# bac-bmb.net
KiCad netlist of a schematic drawn in EAGLE
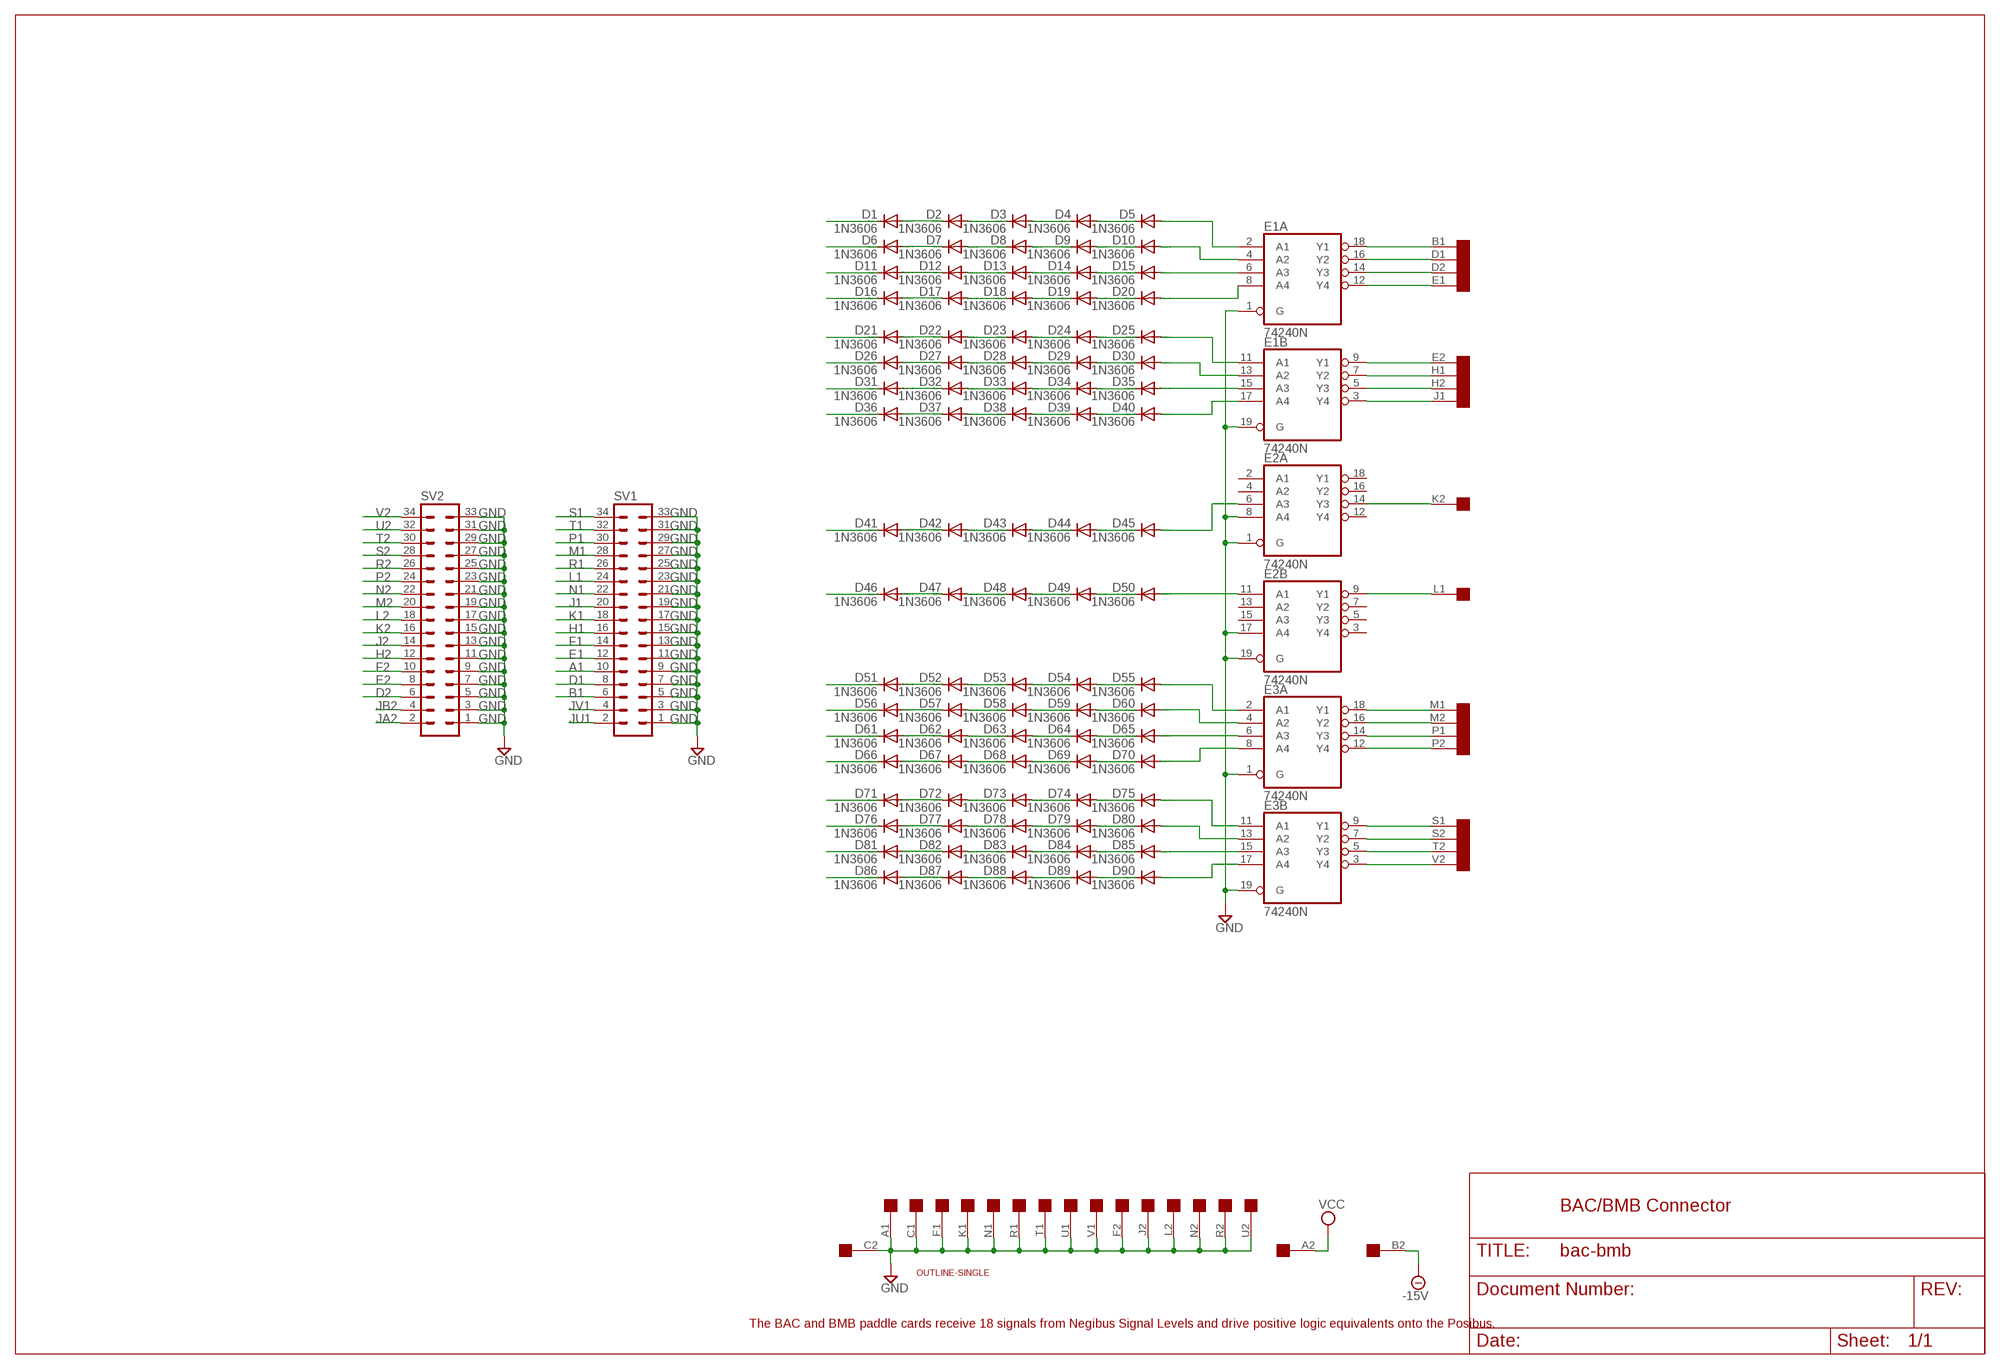
[diagram p0: schematic, sheet 1]

(export (version "E")
  (design (tool "Eeschema 10.0.6"))
  (components
    (comp (ref "D1")
      (value "1N3606")
      (footprint "eagle-import:DO35-10")
      (libsource (lib "eagle-import") (part "DIODE-DO35-10"))
    )
    (comp (ref "D2")
      (value "1N3606")
      (footprint "eagle-import:DO35-10")
      (libsource (lib "eagle-import") (part "DIODE-DO35-10"))
    )
    (comp (ref "D3")
      (value "1N3606")
      (footprint "eagle-import:DO35-10")
      (libsource (lib "eagle-import") (part "DIODE-DO35-10"))
    )
    (comp (ref "D4")
      (value "1N3606")
      (footprint "eagle-import:DO35-10")
      (libsource (lib "eagle-import") (part "DIODE-DO35-10"))
    )
    (comp (ref "D5")
      (value "1N3606")
      (footprint "eagle-import:DO35-10")
      (libsource (lib "eagle-import") (part "DIODE-DO35-10"))
    )
    (comp (ref "D6")
      (value "1N3606")
      (footprint "eagle-import:DO35-10")
      (libsource (lib "eagle-import") (part "DIODE-DO35-10"))
    )
    (comp (ref "D7")
      (value "1N3606")
      (footprint "eagle-import:DO35-10")
      (libsource (lib "eagle-import") (part "DIODE-DO35-10"))
    )
    (comp (ref "D8")
      (value "1N3606")
      (footprint "eagle-import:DO35-10")
      (libsource (lib "eagle-import") (part "DIODE-DO35-10"))
    )
    (comp (ref "D9")
      (value "1N3606")
      (footprint "eagle-import:DO35-10")
      (libsource (lib "eagle-import") (part "DIODE-DO35-10"))
    )
    (comp (ref "D10")
      (value "1N3606")
      (footprint "eagle-import:DO35-10")
      (libsource (lib "eagle-import") (part "DIODE-DO35-10"))
    )
    (comp (ref "D11")
      (value "1N3606")
      (footprint "eagle-import:DO35-10")
      (libsource (lib "eagle-import") (part "DIODE-DO35-10"))
    )
    (comp (ref "D12")
      (value "1N3606")
      (footprint "eagle-import:DO35-10")
      (libsource (lib "eagle-import") (part "DIODE-DO35-10"))
    )
    (comp (ref "D13")
      (value "1N3606")
      (footprint "eagle-import:DO35-10")
      (libsource (lib "eagle-import") (part "DIODE-DO35-10"))
    )
    (comp (ref "D14")
      (value "1N3606")
      (footprint "eagle-import:DO35-10")
      (libsource (lib "eagle-import") (part "DIODE-DO35-10"))
    )
    (comp (ref "D15")
      (value "1N3606")
      (footprint "eagle-import:DO35-10")
      (libsource (lib "eagle-import") (part "DIODE-DO35-10"))
    )
    (comp (ref "D16")
      (value "1N3606")
      (footprint "eagle-import:DO35-10")
      (libsource (lib "eagle-import") (part "DIODE-DO35-10"))
    )
    (comp (ref "D17")
      (value "1N3606")
      (footprint "eagle-import:DO35-10")
      (libsource (lib "eagle-import") (part "DIODE-DO35-10"))
    )
    (comp (ref "D18")
      (value "1N3606")
      (footprint "eagle-import:DO35-10")
      (libsource (lib "eagle-import") (part "DIODE-DO35-10"))
    )
    (comp (ref "D19")
      (value "1N3606")
      (footprint "eagle-import:DO35-10")
      (libsource (lib "eagle-import") (part "DIODE-DO35-10"))
    )
    (comp (ref "D20")
      (value "1N3606")
      (footprint "eagle-import:DO35-10")
      (libsource (lib "eagle-import") (part "DIODE-DO35-10"))
    )
    (comp (ref "D21")
      (value "1N3606")
      (footprint "eagle-import:DO35-10")
      (libsource (lib "eagle-import") (part "DIODE-DO35-10"))
    )
    (comp (ref "D22")
      (value "1N3606")
      (footprint "eagle-import:DO35-10")
      (libsource (lib "eagle-import") (part "DIODE-DO35-10"))
    )
    (comp (ref "D23")
      (value "1N3606")
      (footprint "eagle-import:DO35-10")
      (libsource (lib "eagle-import") (part "DIODE-DO35-10"))
    )
    (comp (ref "D24")
      (value "1N3606")
      (footprint "eagle-import:DO35-10")
      (libsource (lib "eagle-import") (part "DIODE-DO35-10"))
    )
    (comp (ref "D25")
      (value "1N3606")
      (footprint "eagle-import:DO35-10")
      (libsource (lib "eagle-import") (part "DIODE-DO35-10"))
    )
    (comp (ref "D26")
      (value "1N3606")
      (footprint "eagle-import:DO35-10")
      (libsource (lib "eagle-import") (part "DIODE-DO35-10"))
    )
    (comp (ref "D27")
      (value "1N3606")
      (footprint "eagle-import:DO35-10")
      (libsource (lib "eagle-import") (part "DIODE-DO35-10"))
    )
    (comp (ref "D28")
      (value "1N3606")
      (footprint "eagle-import:DO35-10")
      (libsource (lib "eagle-import") (part "DIODE-DO35-10"))
    )
    (comp (ref "D29")
      (value "1N3606")
      (footprint "eagle-import:DO35-10")
      (libsource (lib "eagle-import") (part "DIODE-DO35-10"))
    )
    (comp (ref "D30")
      (value "1N3606")
      (footprint "eagle-import:DO35-10")
      (libsource (lib "eagle-import") (part "DIODE-DO35-10"))
    )
    (comp (ref "D31")
      (value "1N3606")
      (footprint "eagle-import:DO35-10")
      (libsource (lib "eagle-import") (part "DIODE-DO35-10"))
    )
    (comp (ref "D32")
      (value "1N3606")
      (footprint "eagle-import:DO35-10")
      (libsource (lib "eagle-import") (part "DIODE-DO35-10"))
    )
    (comp (ref "D33")
      (value "1N3606")
      (footprint "eagle-import:DO35-10")
      (libsource (lib "eagle-import") (part "DIODE-DO35-10"))
    )
    (comp (ref "D34")
      (value "1N3606")
      (footprint "eagle-import:DO35-10")
      (libsource (lib "eagle-import") (part "DIODE-DO35-10"))
    )
    (comp (ref "D35")
      (value "1N3606")
      (footprint "eagle-import:DO35-10")
      (libsource (lib "eagle-import") (part "DIODE-DO35-10"))
    )
    (comp (ref "D36")
      (value "1N3606")
      (footprint "eagle-import:DO35-10")
      (libsource (lib "eagle-import") (part "DIODE-DO35-10"))
    )
    (comp (ref "D37")
      (value "1N3606")
      (footprint "eagle-import:DO35-10")
      (libsource (lib "eagle-import") (part "DIODE-DO35-10"))
    )
    (comp (ref "D38")
      (value "1N3606")
      (footprint "eagle-import:DO35-10")
      (libsource (lib "eagle-import") (part "DIODE-DO35-10"))
    )
    (comp (ref "D39")
      (value "1N3606")
      (footprint "eagle-import:DO35-10")
      (libsource (lib "eagle-import") (part "DIODE-DO35-10"))
    )
    (comp (ref "D40")
      (value "1N3606")
      (footprint "eagle-import:DO35-10")
      (libsource (lib "eagle-import") (part "DIODE-DO35-10"))
    )
    (comp (ref "D41")
      (value "1N3606")
      (footprint "eagle-import:DO35-10")
      (libsource (lib "eagle-import") (part "DIODE-DO35-10"))
    )
    (comp (ref "D42")
      (value "1N3606")
      (footprint "eagle-import:DO35-10")
      (libsource (lib "eagle-import") (part "DIODE-DO35-10"))
    )
    (comp (ref "D43")
      (value "1N3606")
      (footprint "eagle-import:DO35-10")
      (libsource (lib "eagle-import") (part "DIODE-DO35-10"))
    )
    (comp (ref "D44")
      (value "1N3606")
      (footprint "eagle-import:DO35-10")
      (libsource (lib "eagle-import") (part "DIODE-DO35-10"))
    )
    (comp (ref "D45")
      (value "1N3606")
      (footprint "eagle-import:DO35-10")
      (libsource (lib "eagle-import") (part "DIODE-DO35-10"))
    )
    (comp (ref "D46")
      (value "1N3606")
      (footprint "eagle-import:DO35-10")
      (libsource (lib "eagle-import") (part "DIODE-DO35-10"))
    )
    (comp (ref "D47")
      (value "1N3606")
      (footprint "eagle-import:DO35-10")
      (libsource (lib "eagle-import") (part "DIODE-DO35-10"))
    )
    (comp (ref "D48")
      (value "1N3606")
      (footprint "eagle-import:DO35-10")
      (libsource (lib "eagle-import") (part "DIODE-DO35-10"))
    )
    (comp (ref "D49")
      (value "1N3606")
      (footprint "eagle-import:DO35-10")
      (libsource (lib "eagle-import") (part "DIODE-DO35-10"))
    )
    (comp (ref "D50")
      (value "1N3606")
      (footprint "eagle-import:DO35-10")
      (libsource (lib "eagle-import") (part "DIODE-DO35-10"))
    )
    (comp (ref "D51")
      (value "1N3606")
      (footprint "eagle-import:DO35-10")
      (libsource (lib "eagle-import") (part "DIODE-DO35-10"))
    )
    (comp (ref "D52")
      (value "1N3606")
      (footprint "eagle-import:DO35-10")
      (libsource (lib "eagle-import") (part "DIODE-DO35-10"))
    )
    (comp (ref "D53")
      (value "1N3606")
      (footprint "eagle-import:DO35-10")
      (libsource (lib "eagle-import") (part "DIODE-DO35-10"))
    )
    (comp (ref "D54")
      (value "1N3606")
      (footprint "eagle-import:DO35-10")
      (libsource (lib "eagle-import") (part "DIODE-DO35-10"))
    )
    (comp (ref "D55")
      (value "1N3606")
      (footprint "eagle-import:DO35-10")
      (libsource (lib "eagle-import") (part "DIODE-DO35-10"))
    )
    (comp (ref "D56")
      (value "1N3606")
      (footprint "eagle-import:DO35-10")
      (libsource (lib "eagle-import") (part "DIODE-DO35-10"))
    )
    (comp (ref "D57")
      (value "1N3606")
      (footprint "eagle-import:DO35-10")
      (libsource (lib "eagle-import") (part "DIODE-DO35-10"))
    )
    (comp (ref "D58")
      (value "1N3606")
      (footprint "eagle-import:DO35-10")
      (libsource (lib "eagle-import") (part "DIODE-DO35-10"))
    )
    (comp (ref "D59")
      (value "1N3606")
      (footprint "eagle-import:DO35-10")
      (libsource (lib "eagle-import") (part "DIODE-DO35-10"))
    )
    (comp (ref "D60")
      (value "1N3606")
      (footprint "eagle-import:DO35-10")
      (libsource (lib "eagle-import") (part "DIODE-DO35-10"))
    )
    (comp (ref "D61")
      (value "1N3606")
      (footprint "eagle-import:DO35-10")
      (libsource (lib "eagle-import") (part "DIODE-DO35-10"))
    )
    (comp (ref "D62")
      (value "1N3606")
      (footprint "eagle-import:DO35-10")
      (libsource (lib "eagle-import") (part "DIODE-DO35-10"))
    )
    (comp (ref "D63")
      (value "1N3606")
      (footprint "eagle-import:DO35-10")
      (libsource (lib "eagle-import") (part "DIODE-DO35-10"))
    )
    (comp (ref "D64")
      (value "1N3606")
      (footprint "eagle-import:DO35-10")
      (libsource (lib "eagle-import") (part "DIODE-DO35-10"))
    )
    (comp (ref "D65")
      (value "1N3606")
      (footprint "eagle-import:DO35-10")
      (libsource (lib "eagle-import") (part "DIODE-DO35-10"))
    )
    (comp (ref "D66")
      (value "1N3606")
      (footprint "eagle-import:DO35-10")
      (libsource (lib "eagle-import") (part "DIODE-DO35-10"))
    )
    (comp (ref "D67")
      (value "1N3606")
      (footprint "eagle-import:DO35-10")
      (libsource (lib "eagle-import") (part "DIODE-DO35-10"))
    )
    (comp (ref "D68")
      (value "1N3606")
      (footprint "eagle-import:DO35-10")
      (libsource (lib "eagle-import") (part "DIODE-DO35-10"))
    )
    (comp (ref "D69")
      (value "1N3606")
      (footprint "eagle-import:DO35-10")
      (libsource (lib "eagle-import") (part "DIODE-DO35-10"))
    )
    (comp (ref "D70")
      (value "1N3606")
      (footprint "eagle-import:DO35-10")
      (libsource (lib "eagle-import") (part "DIODE-DO35-10"))
    )
    (comp (ref "D71")
      (value "1N3606")
      (footprint "eagle-import:DO35-10")
      (libsource (lib "eagle-import") (part "DIODE-DO35-10"))
    )
    (comp (ref "D72")
      (value "1N3606")
      (footprint "eagle-import:DO35-10")
      (libsource (lib "eagle-import") (part "DIODE-DO35-10"))
    )
    (comp (ref "D73")
      (value "1N3606")
      (footprint "eagle-import:DO35-10")
      (libsource (lib "eagle-import") (part "DIODE-DO35-10"))
    )
    (comp (ref "D74")
      (value "1N3606")
      (footprint "eagle-import:DO35-10")
      (libsource (lib "eagle-import") (part "DIODE-DO35-10"))
    )
    (comp (ref "D75")
      (value "1N3606")
      (footprint "eagle-import:DO35-10")
      (libsource (lib "eagle-import") (part "DIODE-DO35-10"))
    )
    (comp (ref "D76")
      (value "1N3606")
      (footprint "eagle-import:DO35-10")
      (libsource (lib "eagle-import") (part "DIODE-DO35-10"))
    )
    (comp (ref "D77")
      (value "1N3606")
      (footprint "eagle-import:DO35-10")
      (libsource (lib "eagle-import") (part "DIODE-DO35-10"))
    )
    (comp (ref "D78")
      (value "1N3606")
      (footprint "eagle-import:DO35-10")
      (libsource (lib "eagle-import") (part "DIODE-DO35-10"))
    )
    (comp (ref "D79")
      (value "1N3606")
      (footprint "eagle-import:DO35-10")
      (libsource (lib "eagle-import") (part "DIODE-DO35-10"))
    )
    (comp (ref "D80")
      (value "1N3606")
      (footprint "eagle-import:DO35-10")
      (libsource (lib "eagle-import") (part "DIODE-DO35-10"))
    )
    (comp (ref "D81")
      (value "1N3606")
      (footprint "eagle-import:DO35-10")
      (libsource (lib "eagle-import") (part "DIODE-DO35-10"))
    )
    (comp (ref "D82")
      (value "1N3606")
      (footprint "eagle-import:DO35-10")
      (libsource (lib "eagle-import") (part "DIODE-DO35-10"))
    )
    (comp (ref "D83")
      (value "1N3606")
      (footprint "eagle-import:DO35-10")
      (libsource (lib "eagle-import") (part "DIODE-DO35-10"))
    )
    (comp (ref "D84")
      (value "1N3606")
      (footprint "eagle-import:DO35-10")
      (libsource (lib "eagle-import") (part "DIODE-DO35-10"))
    )
    (comp (ref "D85")
      (value "1N3606")
      (footprint "eagle-import:DO35-10")
      (libsource (lib "eagle-import") (part "DIODE-DO35-10"))
    )
    (comp (ref "D86")
      (value "1N3606")
      (footprint "eagle-import:DO35-10")
      (libsource (lib "eagle-import") (part "DIODE-DO35-10"))
    )
    (comp (ref "D87")
      (value "1N3606")
      (footprint "eagle-import:DO35-10")
      (libsource (lib "eagle-import") (part "DIODE-DO35-10"))
    )
    (comp (ref "D88")
      (value "1N3606")
      (footprint "eagle-import:DO35-10")
      (libsource (lib "eagle-import") (part "DIODE-DO35-10"))
    )
    (comp (ref "D89")
      (value "1N3606")
      (footprint "eagle-import:DO35-10")
      (libsource (lib "eagle-import") (part "DIODE-DO35-10"))
    )
    (comp (ref "D90")
      (value "1N3606")
      (footprint "eagle-import:DO35-10")
      (libsource (lib "eagle-import") (part "DIODE-DO35-10"))
    )
    (comp (ref "E1")
      (value "74240N")
      (footprint "eagle-import:DIL20")
      (libsource (lib "eagle-import") (part "74240NLS"))
    )
    (comp (ref "E2")
      (value "74240N")
      (footprint "eagle-import:DIL20")
      (libsource (lib "eagle-import") (part "74240NLS"))
    )
    (comp (ref "E3")
      (value "74240N")
      (footprint "eagle-import:DIL20")
      (libsource (lib "eagle-import") (part "74240NLS"))
    )
    (comp (ref "SV1")
      (value "MA17-2")
      (footprint "eagle-import:MA17-2")
      (libsource (lib "eagle-import") (part "MA17-2"))
    )
    (comp (ref "SV2")
      (value "MA17-2")
      (footprint "eagle-import:MA17-2")
      (libsource (lib "eagle-import") (part "MA17-2"))
    )
    (comp (ref "U$1")
      (value "SINGLE")
      (footprint "eagle-import:EDGE-CON2")
      (libsource (lib "eagle-import") (part "SINGLE"))
    )
    (comp (ref "U$2")
      (value "OUTLINE-SINGLE")
      (footprint "eagle-import:SINGLE")
      (libsource (lib "eagle-import") (part "OUTLINE-SINGLE"))
    )
  )
  (nets
    (net (code "1") (name "-15V") (class "Default")
      (node (ref "U$1") (pin "B2") (pinfunction "1_B2") (pintype "bidirectional"))
    )
    (net (code "2") (name "/A1") (class "Default")
      (node (ref "SV1") (pin "10") (pinfunction "10_10") (pintype "passive"))
    )
    (net (code "3") (name "/B1") (class "Default")
      (node (ref "D1") (pin "C") (pinfunction "C_C") (pintype "passive"))
      (node (ref "SV1") (pin "6") (pinfunction "6_6") (pintype "passive"))
    )
    (net (code "4") (name "/D1") (class "Default")
      (node (ref "D6") (pin "C") (pinfunction "C_C") (pintype "passive"))
      (node (ref "SV1") (pin "8") (pinfunction "8_8") (pintype "passive"))
    )
    (net (code "5") (name "/D2") (class "Default")
      (node (ref "D11") (pin "C") (pinfunction "C_C") (pintype "passive"))
      (node (ref "SV2") (pin "6") (pinfunction "6_6") (pintype "passive"))
    )
    (net (code "6") (name "/E1") (class "Default")
      (node (ref "D16") (pin "C") (pinfunction "C_C") (pintype "passive"))
      (node (ref "SV1") (pin "12") (pinfunction "12_12") (pintype "passive"))
    )
    (net (code "7") (name "/E2") (class "Default")
      (node (ref "D21") (pin "C") (pinfunction "C_C") (pintype "passive"))
      (node (ref "SV2") (pin "8") (pinfunction "8_8") (pintype "passive"))
    )
    (net (code "8") (name "/F1") (class "Default")
      (node (ref "SV1") (pin "14") (pinfunction "14_14") (pintype "passive"))
    )
    (net (code "9") (name "/F2") (class "Default")
      (node (ref "SV2") (pin "10") (pinfunction "10_10") (pintype "passive"))
    )
    (net (code "10") (name "/H1") (class "Default")
      (node (ref "D26") (pin "C") (pinfunction "C_C") (pintype "passive"))
      (node (ref "SV1") (pin "16") (pinfunction "16_16") (pintype "passive"))
    )
    (net (code "11") (name "/H2") (class "Default")
      (node (ref "D31") (pin "C") (pinfunction "C_C") (pintype "passive"))
      (node (ref "SV2") (pin "12") (pinfunction "12_12") (pintype "passive"))
    )
    (net (code "12") (name "/J1") (class "Default")
      (node (ref "D36") (pin "C") (pinfunction "C_C") (pintype "passive"))
      (node (ref "SV1") (pin "20") (pinfunction "20_20") (pintype "passive"))
    )
    (net (code "13") (name "/J2") (class "Default")
      (node (ref "SV2") (pin "14") (pinfunction "14_14") (pintype "passive"))
    )
    (net (code "14") (name "/JA2") (class "Default")
      (node (ref "SV2") (pin "2") (pinfunction "2_2") (pintype "passive"))
    )
    (net (code "15") (name "/JB2") (class "Default")
      (node (ref "SV2") (pin "4") (pinfunction "4_4") (pintype "passive"))
    )
    (net (code "16") (name "/JU1") (class "Default")
      (node (ref "SV1") (pin "2") (pinfunction "2_2") (pintype "passive"))
    )
    (net (code "17") (name "/JV1") (class "Default")
      (node (ref "SV1") (pin "4") (pinfunction "4_4") (pintype "passive"))
    )
    (net (code "18") (name "/K1") (class "Default")
      (node (ref "SV1") (pin "18") (pinfunction "18_18") (pintype "passive"))
    )
    (net (code "19") (name "/K2") (class "Default")
      (node (ref "D41") (pin "C") (pinfunction "C_C") (pintype "passive"))
      (node (ref "SV2") (pin "16") (pinfunction "16_16") (pintype "passive"))
    )
    (net (code "20") (name "/L1") (class "Default")
      (node (ref "D46") (pin "C") (pinfunction "C_C") (pintype "passive"))
      (node (ref "SV1") (pin "24") (pinfunction "24_24") (pintype "passive"))
    )
    (net (code "21") (name "/L2") (class "Default")
      (node (ref "SV2") (pin "18") (pinfunction "18_18") (pintype "passive"))
    )
    (net (code "22") (name "/M1") (class "Default")
      (node (ref "D51") (pin "C") (pinfunction "C_C") (pintype "passive"))
      (node (ref "SV1") (pin "28") (pinfunction "28_28") (pintype "passive"))
    )
    (net (code "23") (name "/M2") (class "Default")
      (node (ref "D56") (pin "C") (pinfunction "C_C") (pintype "passive"))
      (node (ref "SV2") (pin "20") (pinfunction "20_20") (pintype "passive"))
    )
    (net (code "24") (name "/N1") (class "Default")
      (node (ref "SV1") (pin "22") (pinfunction "22_22") (pintype "passive"))
    )
    (net (code "25") (name "/N2") (class "Default")
      (node (ref "SV2") (pin "22") (pinfunction "22_22") (pintype "passive"))
    )
    (net (code "26") (name "/P1") (class "Default")
      (node (ref "D61") (pin "C") (pinfunction "C_C") (pintype "passive"))
      (node (ref "SV1") (pin "30") (pinfunction "30_30") (pintype "passive"))
    )
    (net (code "27") (name "/P2") (class "Default")
      (node (ref "D66") (pin "C") (pinfunction "C_C") (pintype "passive"))
      (node (ref "SV2") (pin "24") (pinfunction "24_24") (pintype "passive"))
    )
    (net (code "28") (name "/R1") (class "Default")
      (node (ref "SV1") (pin "26") (pinfunction "26_26") (pintype "passive"))
    )
    (net (code "29") (name "/R2") (class "Default")
      (node (ref "SV2") (pin "26") (pinfunction "26_26") (pintype "passive"))
    )
    (net (code "30") (name "/S1") (class "Default")
      (node (ref "D71") (pin "C") (pinfunction "C_C") (pintype "passive"))
      (node (ref "SV1") (pin "34") (pinfunction "34_34") (pintype "passive"))
    )
    (net (code "31") (name "/S2") (class "Default")
      (node (ref "D76") (pin "C") (pinfunction "C_C") (pintype "passive"))
      (node (ref "SV2") (pin "28") (pinfunction "28_28") (pintype "passive"))
    )
    (net (code "32") (name "/T1") (class "Default")
      (node (ref "SV1") (pin "32") (pinfunction "32_32") (pintype "passive"))
    )
    (net (code "33") (name "/T2") (class "Default")
      (node (ref "D81") (pin "C") (pinfunction "C_C") (pintype "passive"))
      (node (ref "SV2") (pin "30") (pinfunction "30_30") (pintype "passive"))
    )
    (net (code "34") (name "/U2") (class "Default")
      (node (ref "SV2") (pin "32") (pinfunction "32_32") (pintype "passive"))
    )
    (net (code "35") (name "/V2") (class "Default")
      (node (ref "D86") (pin "C") (pinfunction "C_C") (pintype "passive"))
      (node (ref "SV2") (pin "34") (pinfunction "34_34") (pintype "passive"))
    )
    (net (code "36") (name "GND") (class "Default")
      (node (ref "E1") (pin "1") (pinfunction "G_1") (pintype "input"))
      (node (ref "E1") (pin "19") (pinfunction "G_19") (pintype "input"))
      (node (ref "E2") (pin "1") (pinfunction "G_1") (pintype "input"))
      (node (ref "E2") (pin "17") (pinfunction "A4_17") (pintype "input"))
      (node (ref "E2") (pin "19") (pinfunction "G_19") (pintype "input"))
      (node (ref "E2") (pin "8") (pinfunction "A4_8") (pintype "input"))
      (node (ref "E3") (pin "1") (pinfunction "G_1") (pintype "input"))
      (node (ref "E3") (pin "19") (pinfunction "G_19") (pintype "input"))
      (node (ref "SV1") (pin "1") (pinfunction "1_1") (pintype "passive"))
      (node (ref "SV1") (pin "11") (pinfunction "11_11") (pintype "passive"))
      (node (ref "SV1") (pin "13") (pinfunction "13_13") (pintype "passive"))
      (node (ref "SV1") (pin "15") (pinfunction "15_15") (pintype "passive"))
      (node (ref "SV1") (pin "17") (pinfunction "17_17") (pintype "passive"))
      (node (ref "SV1") (pin "19") (pinfunction "19_19") (pintype "passive"))
      (node (ref "SV1") (pin "21") (pinfunction "21_21") (pintype "passive"))
      (node (ref "SV1") (pin "23") (pinfunction "23_23") (pintype "passive"))
      (node (ref "SV1") (pin "25") (pinfunction "25_25") (pintype "passive"))
      (node (ref "SV1") (pin "27") (pinfunction "27_27") (pintype "passive"))
      (node (ref "SV1") (pin "29") (pinfunction "29_29") (pintype "passive"))
      (node (ref "SV1") (pin "3") (pinfunction "3_3") (pintype "passive"))
      (node (ref "SV1") (pin "31") (pinfunction "31_31") (pintype "passive"))
      (node (ref "SV1") (pin "33") (pinfunction "33_33") (pintype "passive"))
      (node (ref "SV1") (pin "5") (pinfunction "5_5") (pintype "passive"))
      (node (ref "SV1") (pin "7") (pinfunction "7_7") (pintype "passive"))
      (node (ref "SV1") (pin "9") (pinfunction "9_9") (pintype "passive"))
      (node (ref "SV2") (pin "1") (pinfunction "1_1") (pintype "passive"))
      (node (ref "SV2") (pin "11") (pinfunction "11_11") (pintype "passive"))
      (node (ref "SV2") (pin "13") (pinfunction "13_13") (pintype "passive"))
      (node (ref "SV2") (pin "15") (pinfunction "15_15") (pintype "passive"))
      (node (ref "SV2") (pin "17") (pinfunction "17_17") (pintype "passive"))
      (node (ref "SV2") (pin "19") (pinfunction "19_19") (pintype "passive"))
      (node (ref "SV2") (pin "21") (pinfunction "21_21") (pintype "passive"))
      (node (ref "SV2") (pin "23") (pinfunction "23_23") (pintype "passive"))
      (node (ref "SV2") (pin "25") (pinfunction "25_25") (pintype "passive"))
      (node (ref "SV2") (pin "27") (pinfunction "27_27") (pintype "passive"))
      (node (ref "SV2") (pin "29") (pinfunction "29_29") (pintype "passive"))
      (node (ref "SV2") (pin "3") (pinfunction "3_3") (pintype "passive"))
      (node (ref "SV2") (pin "31") (pinfunction "31_31") (pintype "passive"))
      (node (ref "SV2") (pin "33") (pinfunction "33_33") (pintype "passive"))
      (node (ref "SV2") (pin "5") (pinfunction "5_5") (pintype "passive"))
      (node (ref "SV2") (pin "7") (pinfunction "7_7") (pintype "passive"))
      (node (ref "SV2") (pin "9") (pinfunction "9_9") (pintype "passive"))
      (node (ref "U$1") (pin "A1") (pinfunction "1_A1") (pintype "bidirectional"))
      (node (ref "U$1") (pin "C1") (pinfunction "1_C1") (pintype "bidirectional"))
      (node (ref "U$1") (pin "C2") (pinfunction "1_C2") (pintype "bidirectional"))
      (node (ref "U$1") (pin "F1") (pinfunction "1_F1") (pintype "bidirectional"))
      (node (ref "U$1") (pin "F2") (pinfunction "1_F2") (pintype "bidirectional"))
      (node (ref "U$1") (pin "J2") (pinfunction "1_J2") (pintype "bidirectional"))
      (node (ref "U$1") (pin "K1") (pinfunction "1_K1") (pintype "bidirectional"))
      (node (ref "U$1") (pin "L2") (pinfunction "1_L2") (pintype "bidirectional"))
      (node (ref "U$1") (pin "N1") (pinfunction "1_N1") (pintype "bidirectional"))
      (node (ref "U$1") (pin "N2") (pinfunction "1_N2") (pintype "bidirectional"))
      (node (ref "U$1") (pin "R1") (pinfunction "1_R1") (pintype "bidirectional"))
      (node (ref "U$1") (pin "R2") (pinfunction "1_R2") (pintype "bidirectional"))
      (node (ref "U$1") (pin "T1") (pinfunction "1_T1") (pintype "bidirectional"))
      (node (ref "U$1") (pin "U1") (pinfunction "1_U1") (pintype "bidirectional"))
      (node (ref "U$1") (pin "U2") (pinfunction "1_U2") (pintype "bidirectional"))
      (node (ref "U$1") (pin "V1") (pinfunction "1_V1") (pintype "bidirectional"))
    )
    (net (code "37") (name "Net-(D1-PadA)") (class "Default")
      (node (ref "D1") (pin "A") (pinfunction "A_A") (pintype "passive"))
      (node (ref "D2") (pin "C") (pinfunction "C_C") (pintype "passive"))
    )
    (net (code "38") (name "Net-(D2-PadA)") (class "Default")
      (node (ref "D2") (pin "A") (pinfunction "A_A") (pintype "passive"))
      (node (ref "D3") (pin "C") (pinfunction "C_C") (pintype "passive"))
    )
    (net (code "39") (name "Net-(D3-PadA)") (class "Default")
      (node (ref "D3") (pin "A") (pinfunction "A_A") (pintype "passive"))
      (node (ref "D4") (pin "C") (pinfunction "C_C") (pintype "passive"))
    )
    (net (code "40") (name "Net-(D4-PadA)") (class "Default")
      (node (ref "D4") (pin "A") (pinfunction "A_A") (pintype "passive"))
      (node (ref "D5") (pin "C") (pinfunction "C_C") (pintype "passive"))
    )
    (net (code "41") (name "Net-(D6-PadA)") (class "Default")
      (node (ref "D6") (pin "A") (pinfunction "A_A") (pintype "passive"))
      (node (ref "D7") (pin "C") (pinfunction "C_C") (pintype "passive"))
    )
    (net (code "42") (name "Net-(D7-PadA)") (class "Default")
      (node (ref "D7") (pin "A") (pinfunction "A_A") (pintype "passive"))
      (node (ref "D8") (pin "C") (pinfunction "C_C") (pintype "passive"))
    )
    (net (code "43") (name "Net-(D8-PadA)") (class "Default")
      (node (ref "D8") (pin "A") (pinfunction "A_A") (pintype "passive"))
      (node (ref "D9") (pin "C") (pinfunction "C_C") (pintype "passive"))
    )
    (net (code "44") (name "Net-(D10-PadC)") (class "Default")
      (node (ref "D10") (pin "C") (pinfunction "C_C") (pintype "passive"))
      (node (ref "D9") (pin "A") (pinfunction "A_A") (pintype "passive"))
    )
    (net (code "45") (name "Net-(D11-PadA)") (class "Default")
      (node (ref "D11") (pin "A") (pinfunction "A_A") (pintype "passive"))
      (node (ref "D12") (pin "C") (pinfunction "C_C") (pintype "passive"))
    )
    (net (code "46") (name "Net-(D12-PadA)") (class "Default")
      (node (ref "D12") (pin "A") (pinfunction "A_A") (pintype "passive"))
      (node (ref "D13") (pin "C") (pinfunction "C_C") (pintype "passive"))
    )
    (net (code "47") (name "Net-(D13-PadA)") (class "Default")
      (node (ref "D13") (pin "A") (pinfunction "A_A") (pintype "passive"))
      (node (ref "D14") (pin "C") (pinfunction "C_C") (pintype "passive"))
    )
    (net (code "48") (name "Net-(D14-PadA)") (class "Default")
      (node (ref "D14") (pin "A") (pinfunction "A_A") (pintype "passive"))
      (node (ref "D15") (pin "C") (pinfunction "C_C") (pintype "passive"))
    )
    (net (code "49") (name "Net-(D16-PadA)") (class "Default")
      (node (ref "D16") (pin "A") (pinfunction "A_A") (pintype "passive"))
      (node (ref "D17") (pin "C") (pinfunction "C_C") (pintype "passive"))
    )
    (net (code "50") (name "Net-(D17-PadA)") (class "Default")
      (node (ref "D17") (pin "A") (pinfunction "A_A") (pintype "passive"))
      (node (ref "D18") (pin "C") (pinfunction "C_C") (pintype "passive"))
    )
    (net (code "51") (name "Net-(D18-PadA)") (class "Default")
      (node (ref "D18") (pin "A") (pinfunction "A_A") (pintype "passive"))
      (node (ref "D19") (pin "C") (pinfunction "C_C") (pintype "passive"))
    )
    (net (code "52") (name "Net-(D19-PadA)") (class "Default")
      (node (ref "D19") (pin "A") (pinfunction "A_A") (pintype "passive"))
      (node (ref "D20") (pin "C") (pinfunction "C_C") (pintype "passive"))
    )
    (net (code "53") (name "Net-(D21-PadA)") (class "Default")
      (node (ref "D21") (pin "A") (pinfunction "A_A") (pintype "passive"))
      (node (ref "D22") (pin "C") (pinfunction "C_C") (pintype "passive"))
    )
    (net (code "54") (name "Net-(D22-PadA)") (class "Default")
      (node (ref "D22") (pin "A") (pinfunction "A_A") (pintype "passive"))
      (node (ref "D23") (pin "C") (pinfunction "C_C") (pintype "passive"))
    )
    (net (code "55") (name "Net-(D23-PadA)") (class "Default")
      (node (ref "D23") (pin "A") (pinfunction "A_A") (pintype "passive"))
      (node (ref "D24") (pin "C") (pinfunction "C_C") (pintype "passive"))
    )
    (net (code "56") (name "Net-(D24-PadA)") (class "Default")
      (node (ref "D24") (pin "A") (pinfunction "A_A") (pintype "passive"))
      (node (ref "D25") (pin "C") (pinfunction "C_C") (pintype "passive"))
    )
    (net (code "57") (name "Net-(D26-PadA)") (class "Default")
      (node (ref "D26") (pin "A") (pinfunction "A_A") (pintype "passive"))
      (node (ref "D27") (pin "C") (pinfunction "C_C") (pintype "passive"))
    )
    (net (code "58") (name "Net-(D27-PadA)") (class "Default")
      (node (ref "D27") (pin "A") (pinfunction "A_A") (pintype "passive"))
      (node (ref "D28") (pin "C") (pinfunction "C_C") (pintype "passive"))
    )
    (net (code "59") (name "Net-(D28-PadA)") (class "Default")
      (node (ref "D28") (pin "A") (pinfunction "A_A") (pintype "passive"))
      (node (ref "D29") (pin "C") (pinfunction "C_C") (pintype "passive"))
    )
    (net (code "60") (name "Net-(D29-PadA)") (class "Default")
      (node (ref "D29") (pin "A") (pinfunction "A_A") (pintype "passive"))
      (node (ref "D30") (pin "C") (pinfunction "C_C") (pintype "passive"))
    )
    (net (code "61") (name "Net-(D31-PadA)") (class "Default")
      (node (ref "D31") (pin "A") (pinfunction "A_A") (pintype "passive"))
      (node (ref "D32") (pin "C") (pinfunction "C_C") (pintype "passive"))
    )
    (net (code "62") (name "Net-(D32-PadA)") (class "Default")
      (node (ref "D32") (pin "A") (pinfunction "A_A") (pintype "passive"))
      (node (ref "D33") (pin "C") (pinfunction "C_C") (pintype "passive"))
    )
    (net (code "63") (name "Net-(D33-PadA)") (class "Default")
      (node (ref "D33") (pin "A") (pinfunction "A_A") (pintype "passive"))
      (node (ref "D34") (pin "C") (pinfunction "C_C") (pintype "passive"))
    )
    (net (code "64") (name "Net-(D34-PadA)") (class "Default")
      (node (ref "D34") (pin "A") (pinfunction "A_A") (pintype "passive"))
      (node (ref "D35") (pin "C") (pinfunction "C_C") (pintype "passive"))
    )
    (net (code "65") (name "Net-(D36-PadA)") (class "Default")
      (node (ref "D36") (pin "A") (pinfunction "A_A") (pintype "passive"))
      (node (ref "D37") (pin "C") (pinfunction "C_C") (pintype "passive"))
    )
    (net (code "66") (name "Net-(D37-PadA)") (class "Default")
      (node (ref "D37") (pin "A") (pinfunction "A_A") (pintype "passive"))
      (node (ref "D38") (pin "C") (pinfunction "C_C") (pintype "passive"))
    )
    (net (code "67") (name "Net-(D38-PadA)") (class "Default")
      (node (ref "D38") (pin "A") (pinfunction "A_A") (pintype "passive"))
      (node (ref "D39") (pin "C") (pinfunction "C_C") (pintype "passive"))
    )
    (net (code "68") (name "Net-(D39-PadA)") (class "Default")
      (node (ref "D39") (pin "A") (pinfunction "A_A") (pintype "passive"))
      (node (ref "D40") (pin "C") (pinfunction "C_C") (pintype "passive"))
    )
    (net (code "69") (name "Net-(D41-PadA)") (class "Default")
      (node (ref "D41") (pin "A") (pinfunction "A_A") (pintype "passive"))
      (node (ref "D42") (pin "C") (pinfunction "C_C") (pintype "passive"))
    )
    (net (code "70") (name "Net-(D42-PadA)") (class "Default")
      (node (ref "D42") (pin "A") (pinfunction "A_A") (pintype "passive"))
      (node (ref "D43") (pin "C") (pinfunction "C_C") (pintype "passive"))
    )
    (net (code "71") (name "Net-(D43-PadA)") (class "Default")
      (node (ref "D43") (pin "A") (pinfunction "A_A") (pintype "passive"))
      (node (ref "D44") (pin "C") (pinfunction "C_C") (pintype "passive"))
    )
    (net (code "72") (name "Net-(D44-PadA)") (class "Default")
      (node (ref "D44") (pin "A") (pinfunction "A_A") (pintype "passive"))
      (node (ref "D45") (pin "C") (pinfunction "C_C") (pintype "passive"))
    )
    (net (code "73") (name "Net-(D46-PadA)") (class "Default")
      (node (ref "D46") (pin "A") (pinfunction "A_A") (pintype "passive"))
      (node (ref "D47") (pin "C") (pinfunction "C_C") (pintype "passive"))
    )
    (net (code "74") (name "Net-(D47-PadA)") (class "Default")
      (node (ref "D47") (pin "A") (pinfunction "A_A") (pintype "passive"))
      (node (ref "D48") (pin "C") (pinfunction "C_C") (pintype "passive"))
    )
    (net (code "75") (name "Net-(D48-PadA)") (class "Default")
      (node (ref "D48") (pin "A") (pinfunction "A_A") (pintype "passive"))
      (node (ref "D49") (pin "C") (pinfunction "C_C") (pintype "passive"))
    )
    (net (code "76") (name "Net-(D49-PadA)") (class "Default")
      (node (ref "D49") (pin "A") (pinfunction "A_A") (pintype "passive"))
      (node (ref "D50") (pin "C") (pinfunction "C_C") (pintype "passive"))
    )
    (net (code "77") (name "Net-(D51-PadA)") (class "Default")
      (node (ref "D51") (pin "A") (pinfunction "A_A") (pintype "passive"))
      (node (ref "D52") (pin "C") (pinfunction "C_C") (pintype "passive"))
    )
    (net (code "78") (name "Net-(D52-PadA)") (class "Default")
      (node (ref "D52") (pin "A") (pinfunction "A_A") (pintype "passive"))
      (node (ref "D53") (pin "C") (pinfunction "C_C") (pintype "passive"))
    )
    (net (code "79") (name "Net-(D53-PadA)") (class "Default")
      (node (ref "D53") (pin "A") (pinfunction "A_A") (pintype "passive"))
      (node (ref "D54") (pin "C") (pinfunction "C_C") (pintype "passive"))
    )
    (net (code "80") (name "Net-(D54-PadA)") (class "Default")
      (node (ref "D54") (pin "A") (pinfunction "A_A") (pintype "passive"))
      (node (ref "D55") (pin "C") (pinfunction "C_C") (pintype "passive"))
    )
    (net (code "81") (name "Net-(D56-PadA)") (class "Default")
      (node (ref "D56") (pin "A") (pinfunction "A_A") (pintype "passive"))
      (node (ref "D57") (pin "C") (pinfunction "C_C") (pintype "passive"))
    )
    (net (code "82") (name "Net-(D57-PadA)") (class "Default")
      (node (ref "D57") (pin "A") (pinfunction "A_A") (pintype "passive"))
      (node (ref "D58") (pin "C") (pinfunction "C_C") (pintype "passive"))
    )
    (net (code "83") (name "Net-(D58-PadA)") (class "Default")
      (node (ref "D58") (pin "A") (pinfunction "A_A") (pintype "passive"))
      (node (ref "D59") (pin "C") (pinfunction "C_C") (pintype "passive"))
    )
    (net (code "84") (name "Net-(D59-PadA)") (class "Default")
      (node (ref "D59") (pin "A") (pinfunction "A_A") (pintype "passive"))
      (node (ref "D60") (pin "C") (pinfunction "C_C") (pintype "passive"))
    )
    (net (code "85") (name "Net-(D61-PadA)") (class "Default")
      (node (ref "D61") (pin "A") (pinfunction "A_A") (pintype "passive"))
      (node (ref "D62") (pin "C") (pinfunction "C_C") (pintype "passive"))
    )
    (net (code "86") (name "Net-(D62-PadA)") (class "Default")
      (node (ref "D62") (pin "A") (pinfunction "A_A") (pintype "passive"))
      (node (ref "D63") (pin "C") (pinfunction "C_C") (pintype "passive"))
    )
    (net (code "87") (name "Net-(D63-PadA)") (class "Default")
      (node (ref "D63") (pin "A") (pinfunction "A_A") (pintype "passive"))
      (node (ref "D64") (pin "C") (pinfunction "C_C") (pintype "passive"))
    )
    (net (code "88") (name "Net-(D64-PadA)") (class "Default")
      (node (ref "D64") (pin "A") (pinfunction "A_A") (pintype "passive"))
      (node (ref "D65") (pin "C") (pinfunction "C_C") (pintype "passive"))
    )
    (net (code "89") (name "Net-(D66-PadA)") (class "Default")
      (node (ref "D66") (pin "A") (pinfunction "A_A") (pintype "passive"))
      (node (ref "D67") (pin "C") (pinfunction "C_C") (pintype "passive"))
    )
    (net (code "90") (name "Net-(D67-PadA)") (class "Default")
      (node (ref "D67") (pin "A") (pinfunction "A_A") (pintype "passive"))
      (node (ref "D68") (pin "C") (pinfunction "C_C") (pintype "passive"))
    )
    (net (code "91") (name "Net-(D68-PadA)") (class "Default")
      (node (ref "D68") (pin "A") (pinfunction "A_A") (pintype "passive"))
      (node (ref "D69") (pin "C") (pinfunction "C_C") (pintype "passive"))
    )
    (net (code "92") (name "Net-(D69-PadA)") (class "Default")
      (node (ref "D69") (pin "A") (pinfunction "A_A") (pintype "passive"))
      (node (ref "D70") (pin "C") (pinfunction "C_C") (pintype "passive"))
    )
    (net (code "93") (name "Net-(D71-PadA)") (class "Default")
      (node (ref "D71") (pin "A") (pinfunction "A_A") (pintype "passive"))
      (node (ref "D72") (pin "C") (pinfunction "C_C") (pintype "passive"))
    )
    (net (code "94") (name "Net-(D72-PadA)") (class "Default")
      (node (ref "D72") (pin "A") (pinfunction "A_A") (pintype "passive"))
      (node (ref "D73") (pin "C") (pinfunction "C_C") (pintype "passive"))
    )
    (net (code "95") (name "Net-(D73-PadA)") (class "Default")
      (node (ref "D73") (pin "A") (pinfunction "A_A") (pintype "passive"))
      (node (ref "D74") (pin "C") (pinfunction "C_C") (pintype "passive"))
    )
    (net (code "96") (name "Net-(D74-PadA)") (class "Default")
      (node (ref "D74") (pin "A") (pinfunction "A_A") (pintype "passive"))
      (node (ref "D75") (pin "C") (pinfunction "C_C") (pintype "passive"))
    )
    (net (code "97") (name "Net-(D76-PadA)") (class "Default")
      (node (ref "D76") (pin "A") (pinfunction "A_A") (pintype "passive"))
      (node (ref "D77") (pin "C") (pinfunction "C_C") (pintype "passive"))
    )
    (net (code "98") (name "Net-(D77-PadA)") (class "Default")
      (node (ref "D77") (pin "A") (pinfunction "A_A") (pintype "passive"))
      (node (ref "D78") (pin "C") (pinfunction "C_C") (pintype "passive"))
    )
    (net (code "99") (name "Net-(D78-PadA)") (class "Default")
      (node (ref "D78") (pin "A") (pinfunction "A_A") (pintype "passive"))
      (node (ref "D79") (pin "C") (pinfunction "C_C") (pintype "passive"))
    )
    (net (code "100") (name "Net-(D79-PadA)") (class "Default")
      (node (ref "D79") (pin "A") (pinfunction "A_A") (pintype "passive"))
      (node (ref "D80") (pin "C") (pinfunction "C_C") (pintype "passive"))
    )
    (net (code "101") (name "Net-(D81-PadA)") (class "Default")
      (node (ref "D81") (pin "A") (pinfunction "A_A") (pintype "passive"))
      (node (ref "D82") (pin "C") (pinfunction "C_C") (pintype "passive"))
    )
    (net (code "102") (name "Net-(D82-PadA)") (class "Default")
      (node (ref "D82") (pin "A") (pinfunction "A_A") (pintype "passive"))
      (node (ref "D83") (pin "C") (pinfunction "C_C") (pintype "passive"))
    )
    (net (code "103") (name "Net-(D83-PadA)") (class "Default")
      (node (ref "D83") (pin "A") (pinfunction "A_A") (pintype "passive"))
      (node (ref "D84") (pin "C") (pinfunction "C_C") (pintype "passive"))
    )
    (net (code "104") (name "Net-(D84-PadA)") (class "Default")
      (node (ref "D84") (pin "A") (pinfunction "A_A") (pintype "passive"))
      (node (ref "D85") (pin "C") (pinfunction "C_C") (pintype "passive"))
    )
    (net (code "105") (name "Net-(D86-PadA)") (class "Default")
      (node (ref "D86") (pin "A") (pinfunction "A_A") (pintype "passive"))
      (node (ref "D87") (pin "C") (pinfunction "C_C") (pintype "passive"))
    )
    (net (code "106") (name "Net-(D87-PadA)") (class "Default")
      (node (ref "D87") (pin "A") (pinfunction "A_A") (pintype "passive"))
      (node (ref "D88") (pin "C") (pinfunction "C_C") (pintype "passive"))
    )
    (net (code "107") (name "Net-(D88-PadA)") (class "Default")
      (node (ref "D88") (pin "A") (pinfunction "A_A") (pintype "passive"))
      (node (ref "D89") (pin "C") (pinfunction "C_C") (pintype "passive"))
    )
    (net (code "108") (name "Net-(D89-PadA)") (class "Default")
      (node (ref "D89") (pin "A") (pinfunction "A_A") (pintype "passive"))
      (node (ref "D90") (pin "C") (pinfunction "C_C") (pintype "passive"))
    )
    (net (code "109") (name "Net-(E1A-A1)") (class "Default")
      (node (ref "D5") (pin "A") (pinfunction "A_A") (pintype "passive"))
      (node (ref "E1") (pin "2") (pinfunction "A1_2") (pintype "input"))
    )
    (net (code "110") (name "Net-(E1A-A2)") (class "Default")
      (node (ref "D10") (pin "A") (pinfunction "A_A") (pintype "passive"))
      (node (ref "E1") (pin "4") (pinfunction "A2_4") (pintype "input"))
    )
    (net (code "111") (name "Net-(E1A-A3)") (class "Default")
      (node (ref "D15") (pin "A") (pinfunction "A_A") (pintype "passive"))
      (node (ref "E1") (pin "6") (pinfunction "A3_6") (pintype "input"))
    )
    (net (code "112") (name "Net-(E1A-A4)") (class "Default")
      (node (ref "D20") (pin "A") (pinfunction "A_A") (pintype "passive"))
      (node (ref "E1") (pin "8") (pinfunction "A4_8") (pintype "input"))
    )
    (net (code "113") (name "Net-(E1A-Y1)") (class "Default")
      (node (ref "E1") (pin "18") (pinfunction "Y1_18") (pintype "tri_state"))
      (node (ref "U$1") (pin "B1") (pinfunction "1_B1") (pintype "bidirectional"))
    )
    (net (code "114") (name "Net-(E1A-Y2)") (class "Default")
      (node (ref "E1") (pin "16") (pinfunction "Y2_16") (pintype "tri_state"))
      (node (ref "U$1") (pin "D1") (pinfunction "1_D1") (pintype "bidirectional"))
    )
    (net (code "115") (name "Net-(E1A-Y3)") (class "Default")
      (node (ref "E1") (pin "14") (pinfunction "Y3_14") (pintype "tri_state"))
      (node (ref "U$1") (pin "D2") (pinfunction "1_D2") (pintype "bidirectional"))
    )
    (net (code "116") (name "Net-(E1A-Y4)") (class "Default")
      (node (ref "E1") (pin "12") (pinfunction "Y4_12") (pintype "tri_state"))
      (node (ref "U$1") (pin "E1") (pinfunction "1_E1") (pintype "bidirectional"))
    )
    (net (code "117") (name "Net-(E1B-A1)") (class "Default")
      (node (ref "D25") (pin "A") (pinfunction "A_A") (pintype "passive"))
      (node (ref "E1") (pin "11") (pinfunction "A1_11") (pintype "input"))
    )
    (net (code "118") (name "Net-(E1B-A2)") (class "Default")
      (node (ref "D30") (pin "A") (pinfunction "A_A") (pintype "passive"))
      (node (ref "E1") (pin "13") (pinfunction "A2_13") (pintype "input"))
    )
    (net (code "119") (name "Net-(E1B-A3)") (class "Default")
      (node (ref "D35") (pin "A") (pinfunction "A_A") (pintype "passive"))
      (node (ref "E1") (pin "15") (pinfunction "A3_15") (pintype "input"))
    )
    (net (code "120") (name "Net-(E1B-A4)") (class "Default")
      (node (ref "D40") (pin "A") (pinfunction "A_A") (pintype "passive"))
      (node (ref "E1") (pin "17") (pinfunction "A4_17") (pintype "input"))
    )
    (net (code "121") (name "Net-(E1B-Y1)") (class "Default")
      (node (ref "E1") (pin "9") (pinfunction "Y1_9") (pintype "tri_state"))
      (node (ref "U$1") (pin "E2") (pinfunction "1_E2") (pintype "bidirectional"))
    )
    (net (code "122") (name "Net-(E1B-Y2)") (class "Default")
      (node (ref "E1") (pin "7") (pinfunction "Y2_7") (pintype "tri_state"))
      (node (ref "U$1") (pin "H1") (pinfunction "1_H1") (pintype "bidirectional"))
    )
    (net (code "123") (name "Net-(E1B-Y3)") (class "Default")
      (node (ref "E1") (pin "5") (pinfunction "Y3_5") (pintype "tri_state"))
      (node (ref "U$1") (pin "H2") (pinfunction "1_H2") (pintype "bidirectional"))
    )
    (net (code "124") (name "Net-(E1B-Y4)") (class "Default")
      (node (ref "E1") (pin "3") (pinfunction "Y4_3") (pintype "tri_state"))
      (node (ref "U$1") (pin "J1") (pinfunction "1_J1") (pintype "bidirectional"))
    )
    (net (code "125") (name "Net-(E2A-A3)") (class "Default")
      (node (ref "D45") (pin "A") (pinfunction "A_A") (pintype "passive"))
      (node (ref "E2") (pin "6") (pinfunction "A3_6") (pintype "input"))
    )
    (net (code "126") (name "Net-(E2A-Y3)") (class "Default")
      (node (ref "E2") (pin "14") (pinfunction "Y3_14") (pintype "tri_state"))
      (node (ref "U$1") (pin "K2") (pinfunction "1_K2") (pintype "bidirectional"))
    )
    (net (code "127") (name "Net-(E2B-A1)") (class "Default")
      (node (ref "D50") (pin "A") (pinfunction "A_A") (pintype "passive"))
      (node (ref "E2") (pin "11") (pinfunction "A1_11") (pintype "input"))
    )
    (net (code "128") (name "Net-(E2B-Y1)") (class "Default")
      (node (ref "E2") (pin "9") (pinfunction "Y1_9") (pintype "tri_state"))
      (node (ref "U$1") (pin "L1") (pinfunction "1_L1") (pintype "bidirectional"))
    )
    (net (code "129") (name "Net-(E3A-A1)") (class "Default")
      (node (ref "D55") (pin "A") (pinfunction "A_A") (pintype "passive"))
      (node (ref "E3") (pin "2") (pinfunction "A1_2") (pintype "input"))
    )
    (net (code "130") (name "Net-(E3A-A2)") (class "Default")
      (node (ref "D60") (pin "A") (pinfunction "A_A") (pintype "passive"))
      (node (ref "E3") (pin "4") (pinfunction "A2_4") (pintype "input"))
    )
    (net (code "131") (name "Net-(E3A-A3)") (class "Default")
      (node (ref "D65") (pin "A") (pinfunction "A_A") (pintype "passive"))
      (node (ref "E3") (pin "6") (pinfunction "A3_6") (pintype "input"))
    )
    (net (code "132") (name "Net-(E3A-A4)") (class "Default")
      (node (ref "D70") (pin "A") (pinfunction "A_A") (pintype "passive"))
      (node (ref "E3") (pin "8") (pinfunction "A4_8") (pintype "input"))
    )
    (net (code "133") (name "Net-(E3A-Y1)") (class "Default")
      (node (ref "E3") (pin "18") (pinfunction "Y1_18") (pintype "tri_state"))
      (node (ref "U$1") (pin "M1") (pinfunction "1_M1") (pintype "bidirectional"))
    )
    (net (code "134") (name "Net-(E3A-Y2)") (class "Default")
      (node (ref "E3") (pin "16") (pinfunction "Y2_16") (pintype "tri_state"))
      (node (ref "U$1") (pin "M2") (pinfunction "1_M2") (pintype "bidirectional"))
    )
    (net (code "135") (name "Net-(E3A-Y3)") (class "Default")
      (node (ref "E3") (pin "14") (pinfunction "Y3_14") (pintype "tri_state"))
      (node (ref "U$1") (pin "P1") (pinfunction "1_P1") (pintype "bidirectional"))
    )
    (net (code "136") (name "Net-(E3A-Y4)") (class "Default")
      (node (ref "E3") (pin "12") (pinfunction "Y4_12") (pintype "tri_state"))
      (node (ref "U$1") (pin "P2") (pinfunction "1_P2") (pintype "bidirectional"))
    )
    (net (code "137") (name "Net-(E3B-A1)") (class "Default")
      (node (ref "D75") (pin "A") (pinfunction "A_A") (pintype "passive"))
      (node (ref "E3") (pin "11") (pinfunction "A1_11") (pintype "input"))
    )
    (net (code "138") (name "Net-(E3B-A2)") (class "Default")
      (node (ref "D80") (pin "A") (pinfunction "A_A") (pintype "passive"))
      (node (ref "E3") (pin "13") (pinfunction "A2_13") (pintype "input"))
    )
    (net (code "139") (name "Net-(E3B-A3)") (class "Default")
      (node (ref "D85") (pin "A") (pinfunction "A_A") (pintype "passive"))
      (node (ref "E3") (pin "15") (pinfunction "A3_15") (pintype "input"))
    )
    (net (code "140") (name "Net-(E3B-A4)") (class "Default")
      (node (ref "D90") (pin "A") (pinfunction "A_A") (pintype "passive"))
      (node (ref "E3") (pin "17") (pinfunction "A4_17") (pintype "input"))
    )
    (net (code "141") (name "Net-(E3B-Y1)") (class "Default")
      (node (ref "E3") (pin "9") (pinfunction "Y1_9") (pintype "tri_state"))
      (node (ref "U$1") (pin "S1") (pinfunction "1_S1") (pintype "bidirectional"))
    )
    (net (code "142") (name "Net-(E3B-Y2)") (class "Default")
      (node (ref "E3") (pin "7") (pinfunction "Y2_7") (pintype "tri_state"))
      (node (ref "U$1") (pin "S2") (pinfunction "1_S2") (pintype "bidirectional"))
    )
    (net (code "143") (name "Net-(E3B-Y3)") (class "Default")
      (node (ref "E3") (pin "5") (pinfunction "Y3_5") (pintype "tri_state"))
      (node (ref "U$1") (pin "T2") (pinfunction "1_T2") (pintype "bidirectional"))
    )
    (net (code "144") (name "Net-(E3B-Y4)") (class "Default")
      (node (ref "E3") (pin "3") (pinfunction "Y4_3") (pintype "tri_state"))
      (node (ref "U$1") (pin "V2") (pinfunction "1_V2") (pintype "bidirectional"))
    )
    (net (code "145") (name "VCC") (class "Default")
      (node (ref "U$1") (pin "A2") (pinfunction "1_A2") (pintype "bidirectional"))
    )
    (net (code "146") (name "unconnected-(E2A-A1-Pad2)") (class "Default")
      (node (ref "E2") (pin "2") (pinfunction "A1_2") (pintype "input"))
    )
    (net (code "147") (name "unconnected-(E2A-A2-Pad4)") (class "Default")
      (node (ref "E2") (pin "4") (pinfunction "A2_4") (pintype "input"))
    )
    (net (code "148") (name "unconnected-(E2A-Y1-Pad18)") (class "Default")
      (node (ref "E2") (pin "18") (pinfunction "Y1_18") (pintype "tri_state"))
    )
    (net (code "149") (name "unconnected-(E2A-Y2-Pad16)") (class "Default")
      (node (ref "E2") (pin "16") (pinfunction "Y2_16") (pintype "tri_state"))
    )
    (net (code "150") (name "unconnected-(E2A-Y4-Pad12)") (class "Default")
      (node (ref "E2") (pin "12") (pinfunction "Y4_12") (pintype "tri_state"))
    )
    (net (code "151") (name "unconnected-(E2B-A2-Pad13)") (class "Default")
      (node (ref "E2") (pin "13") (pinfunction "A2_13") (pintype "input"))
    )
    (net (code "152") (name "unconnected-(E2B-A3-Pad15)") (class "Default")
      (node (ref "E2") (pin "15") (pinfunction "A3_15") (pintype "input"))
    )
    (net (code "153") (name "unconnected-(E2B-Y2-Pad7)") (class "Default")
      (node (ref "E2") (pin "7") (pinfunction "Y2_7") (pintype "tri_state"))
    )
    (net (code "154") (name "unconnected-(E2B-Y3-Pad5)") (class "Default")
      (node (ref "E2") (pin "5") (pinfunction "Y3_5") (pintype "tri_state"))
    )
    (net (code "155") (name "unconnected-(E2B-Y4-Pad3)") (class "Default")
      (node (ref "E2") (pin "3") (pinfunction "Y4_3") (pintype "tri_state"))
    )
  )
)
